# NFCY_BaseBoard.net
KiCad netlist of a schematic drawn in Altium Designer
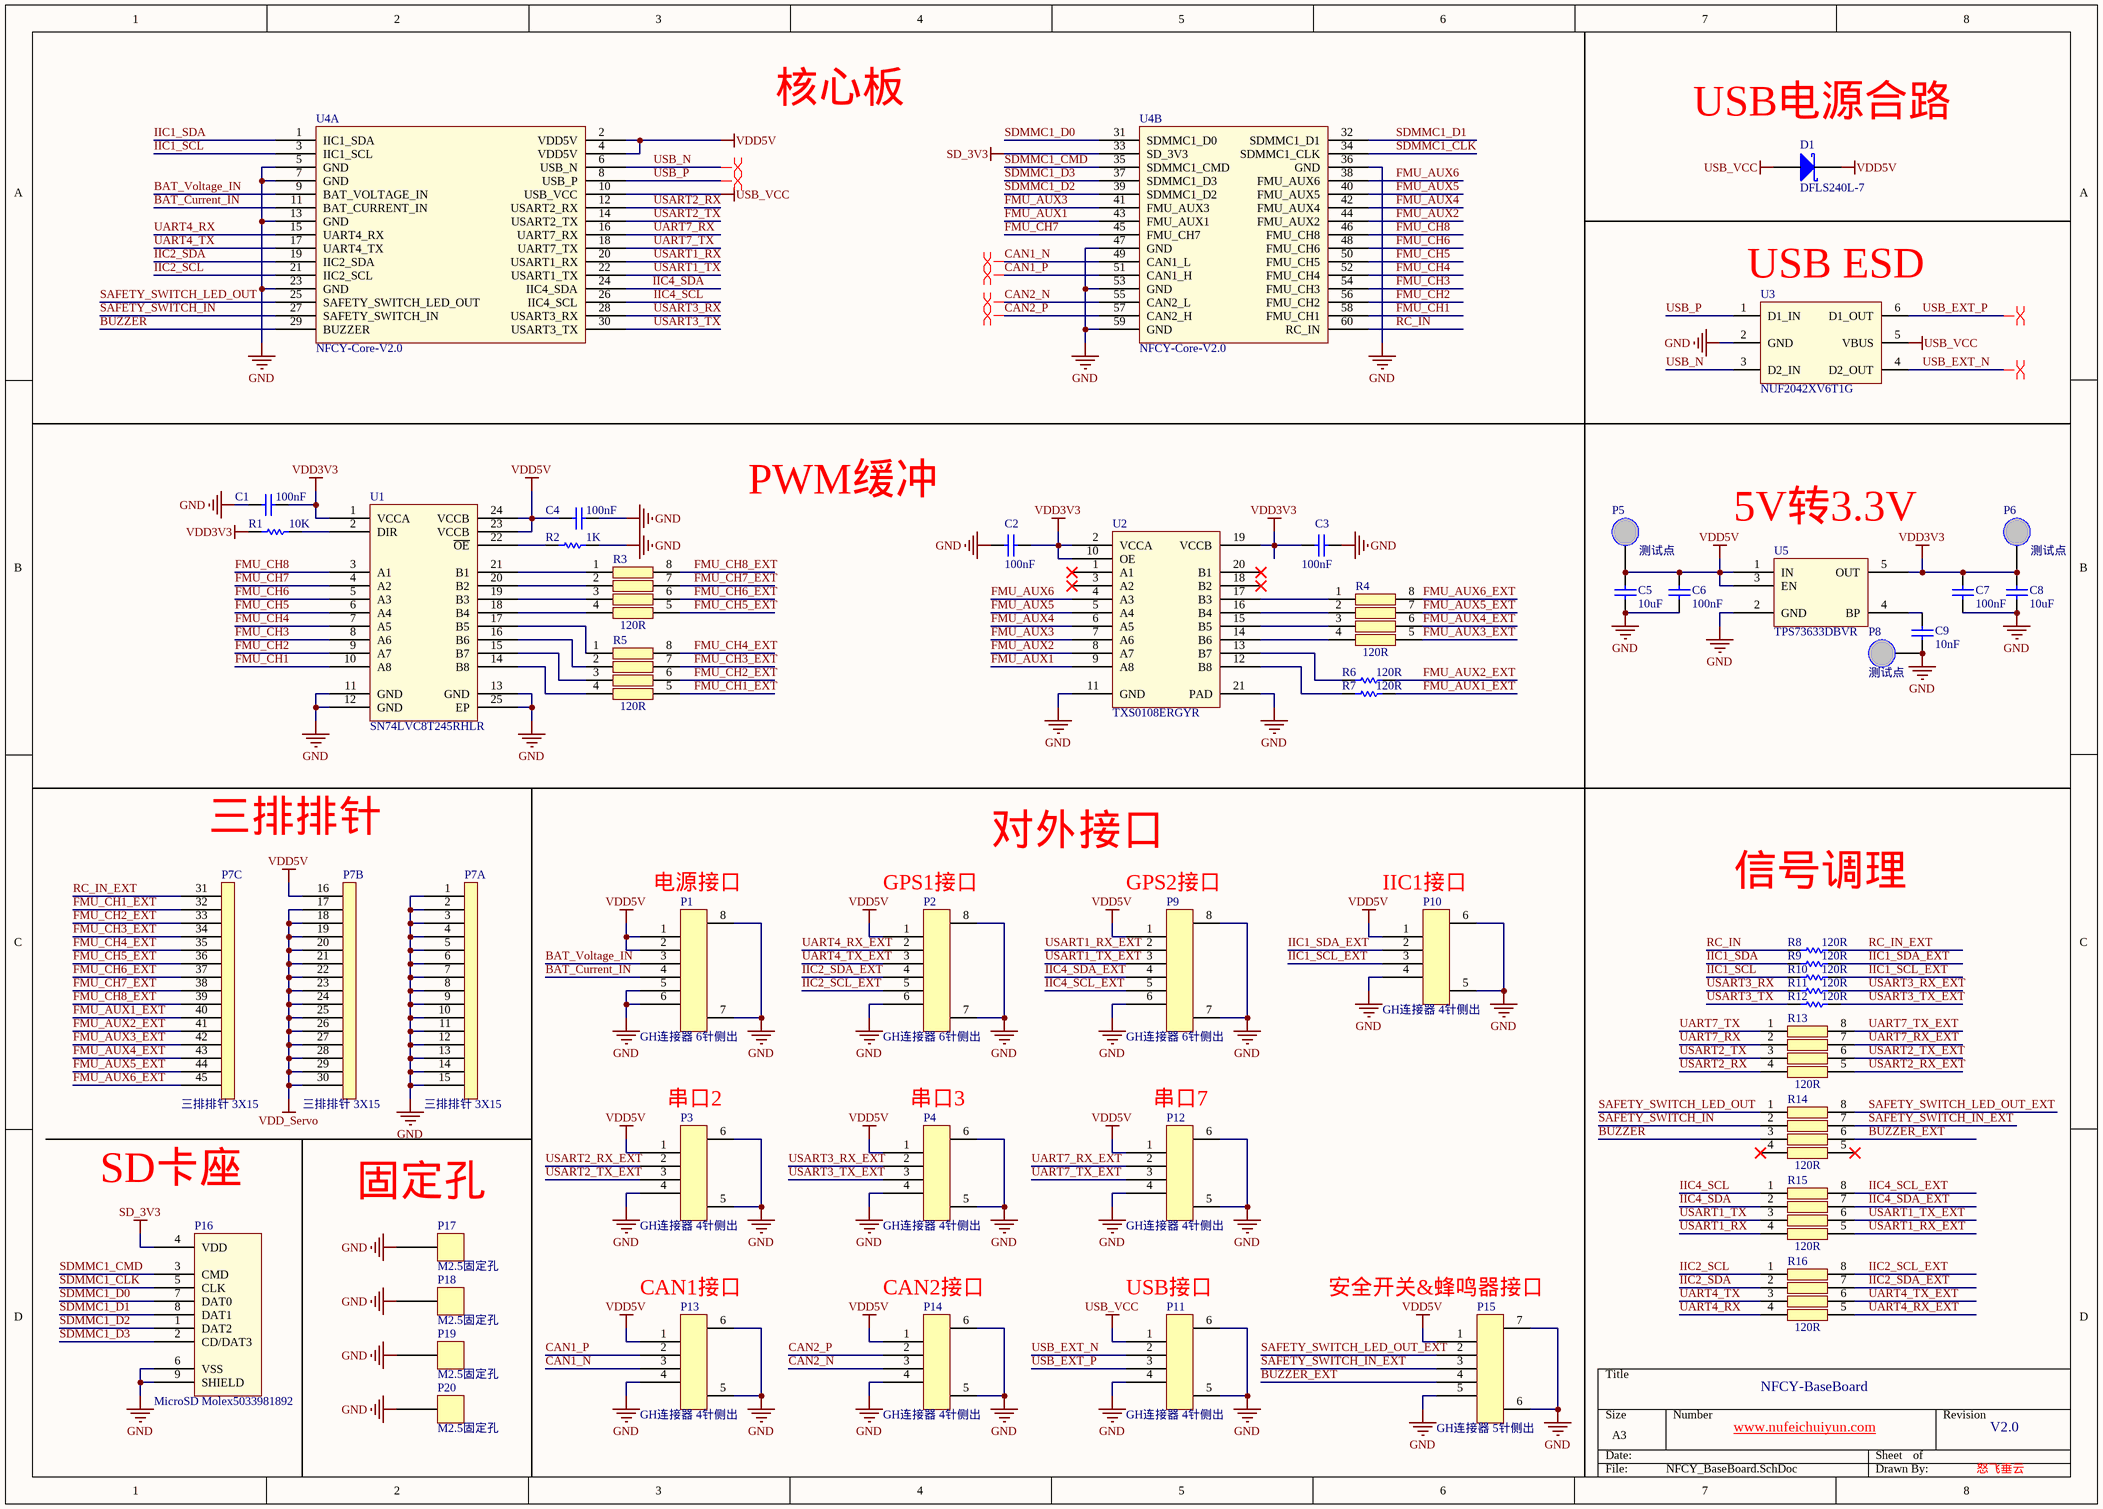
[diagram p0: NFCY_BaseBoard.SchDoc]

(export (version "E")
  (design (tool "Eeschema 10.0.6"))
  (components
    (comp (ref "C1")
      (value "100nF")
      (footprint "CAP0402")
      (description "贴片电容")
      (fields
        (field (name "MANUFACTURER") "SAMSUNG(三星)")
        (field (name "Comment") "CL05B104KO5NNNC")
        (field (name "PUBLISHER") "Altium Limited")
      )
      (libsource (lib "Miscellaneous Devices") (part "Cap"))
    )
    (comp (ref "C2")
      (value "100nF")
      (footprint "CAP0402")
      (description "贴片电容")
      (fields
        (field (name "MANUFACTURER") "SAMSUNG(三星)")
        (field (name "Comment") "CL05B104KO5NNNC")
        (field (name "PUBLISHER") "Altium Limited")
      )
      (libsource (lib "Miscellaneous Devices") (part "Cap"))
    )
    (comp (ref "C3")
      (value "100nF")
      (footprint "CAP0402")
      (description "贴片电容")
      (fields
        (field (name "MANUFACTURER") "SAMSUNG(三星)")
        (field (name "Comment") "CL05B104KO5NNNC")
        (field (name "PUBLISHER") "Altium Limited")
      )
      (libsource (lib "Miscellaneous Devices") (part "Cap"))
    )
    (comp (ref "C4")
      (value "100nF")
      (footprint "CAP0402")
      (description "贴片电容")
      (fields
        (field (name "MANUFACTURER") "SAMSUNG(三星)")
        (field (name "Comment") "CL05B104KO5NNNC")
        (field (name "PUBLISHER") "Altium Limited")
      )
      (libsource (lib "Miscellaneous Devices") (part "Cap"))
    )
    (comp (ref "C5")
      (value "10uF")
      (footprint "CAP0805")
      (description "贴片电容")
      (fields
        (field (name "MANUFACTURER") "SAMSUNG(三星)")
        (field (name "Comment") "CL21A106KAYNNNE")
        (field (name "PUBLISHER") "Altium Limited")
      )
      (libsource (lib "Miscellaneous Devices") (part "Cap"))
    )
    (comp (ref "C6")
      (value "100nF")
      (footprint "CAP0402")
      (description "贴片电容")
      (fields
        (field (name "MANUFACTURER") "SAMSUNG(三星)")
        (field (name "Comment") "CL05B104KO5NNNC")
        (field (name "PUBLISHER") "Altium Limited")
      )
      (libsource (lib "Miscellaneous Devices") (part "Cap"))
    )
    (comp (ref "C7")
      (value "100nF")
      (footprint "CAP0402")
      (description "贴片电容")
      (fields
        (field (name "MANUFACTURER") "SAMSUNG(三星)")
        (field (name "Comment") "CL05B104KO5NNNC")
        (field (name "PUBLISHER") "Altium Limited")
      )
      (libsource (lib "Miscellaneous Devices") (part "Cap"))
    )
    (comp (ref "C8")
      (value "10uF")
      (footprint "CAP0805")
      (description "贴片电容")
      (fields
        (field (name "MANUFACTURER") "SAMSUNG(三星)")
        (field (name "Comment") "CL21A106KAYNNNE")
        (field (name "PUBLISHER") "Altium Limited")
      )
      (libsource (lib "Miscellaneous Devices") (part "Cap"))
    )
    (comp (ref "C9")
      (value "10nF")
      (footprint "CAP0402")
      (description "贴片电容")
      (fields
        (field (name "MANUFACTURER") "YAGEO(国巨)")
        (field (name "Comment") "CC0402KRX7R9BB103")
        (field (name "PUBLISHER") "Altium Limited")
      )
      (libsource (lib "Miscellaneous Devices") (part "Cap"))
    )
    (comp (ref "D1")
      (value "DFLS240L-7")
      (footprint "PwerDI123")
      (description "肖特基二极管")
      (fields (field (name "MANUFACTURER") "DIODES(美台)"))
      (libsource (lib "二极管") (part "DFLS240L-7"))
    )
    (comp (ref "P1")
      (value "GH连接器 6针侧出")
      (footprint "SM06B-GHS-TB")
      (description "连接器")
      (fields (field (name "MANUFACTURER") "JST"))
      (libsource (lib "GH_Connector") (part "GH_6PIN"))
    )
    (comp (ref "P2")
      (value "GH连接器 6针侧出")
      (footprint "SM06B-GHS-TB")
      (description "连接器")
      (fields (field (name "MANUFACTURER") "JST"))
      (libsource (lib "GH_Connector") (part "GH_6PIN"))
    )
    (comp (ref "P3")
      (value "GH连接器 4针侧出")
      (footprint "SM04B-GHS-TB")
      (description "连接器")
      (fields (field (name "MANUFACTURER") "JST"))
      (libsource (lib "GH_Connector") (part "GH_4PIN"))
    )
    (comp (ref "P4")
      (value "GH连接器 4针侧出")
      (footprint "SM04B-GHS-TB")
      (description "连接器")
      (fields (field (name "MANUFACTURER") "JST"))
      (libsource (lib "GH_Connector") (part "GH_4PIN"))
    )
    (comp (ref "P5") (value "测试点") (footprint "PAD0p8MM") (libsource (lib "TestPad") (part "TestPad")))
    (comp (ref "P6") (value "测试点") (footprint "PAD0p8MM") (libsource (lib "TestPad") (part "TestPad")))
    (comp (ref "P7")
      (value "三排排针 3X15")
      (footprint "HDR3X15")
      (description "排针")
      (libsource (lib "排针") (part "三排排针 3X15"))
    )
    (comp (ref "P8") (value "测试点") (footprint "PAD0p8MM") (libsource (lib "TestPad") (part "TestPad")))
    (comp (ref "P9")
      (value "GH连接器 6针侧出")
      (footprint "SM06B-GHS-TB")
      (description "连接器")
      (fields (field (name "MANUFACTURER") "JST"))
      (libsource (lib "GH_Connector") (part "GH_6PIN"))
    )
    (comp (ref "P10")
      (value "GH连接器 4针侧出")
      (footprint "SM04B-GHS-TB")
      (description "连接器")
      (fields (field (name "MANUFACTURER") "JST"))
      (libsource (lib "GH_Connector") (part "GH_4PIN"))
    )
    (comp (ref "P11")
      (value "GH连接器 4针侧出")
      (footprint "SM04B-GHS-TB")
      (description "连接器")
      (fields (field (name "MANUFACTURER") "JST"))
      (libsource (lib "GH_Connector") (part "GH_4PIN"))
    )
    (comp (ref "P12")
      (value "GH连接器 4针侧出")
      (footprint "SM04B-GHS-TB")
      (description "连接器")
      (fields (field (name "MANUFACTURER") "JST"))
      (libsource (lib "GH_Connector") (part "GH_4PIN"))
    )
    (comp (ref "P13")
      (value "GH连接器 4针侧出")
      (footprint "SM04B-GHS-TB")
      (description "连接器")
      (fields (field (name "MANUFACTURER") "JST"))
      (libsource (lib "GH_Connector") (part "GH_4PIN"))
    )
    (comp (ref "P14")
      (value "GH连接器 4针侧出")
      (footprint "SM04B-GHS-TB")
      (description "连接器")
      (fields (field (name "MANUFACTURER") "JST"))
      (libsource (lib "GH_Connector") (part "GH_4PIN"))
    )
    (comp (ref "P15")
      (value "GH连接器 5针侧出")
      (footprint "SM05B-GHS-TB")
      (description "连接器")
      (fields (field (name "MANUFACTURER") "JST"))
      (libsource (lib "GH_Connector") (part "GH_5PIN"))
    )
    (comp (ref "P16")
      (value "MicroSD Molex5033981892")
      (footprint "Molex5033981892")
      (description "MicroSD卡座")
      (fields (field (name "MANUFACTURER") "Molex"))
      (libsource (lib "SD") (part "MicroSD Molex5033981892"))
    )
    (comp (ref "P17") (value "M2.5固定孔") (footprint "M2p5") (libsource (lib "TestPad") (part "Pad")))
    (comp (ref "P18") (value "M2.5固定孔") (footprint "M2p5") (libsource (lib "TestPad") (part "Pad")))
    (comp (ref "P19") (value "M2.5固定孔") (footprint "M2p5") (libsource (lib "TestPad") (part "Pad")))
    (comp (ref "P20") (value "M2.5固定孔") (footprint "M2p5") (libsource (lib "TestPad") (part "Pad")))
    (comp (ref "R1")
      (value "10K")
      (footprint "RES0402")
      (description "贴片电阻")
      (fields
        (field (name "MANUFACTURER") "YAGEO(国巨)")
        (field (name "Comment") "RC0402FR-0710KL")
        (field (name "PUBLISHER") "Altium Limited")
      )
      (libsource (lib "Miscellaneous Devices") (part "Res1"))
    )
    (comp (ref "R2")
      (value "1K")
      (footprint "RES0402")
      (description "贴片电阻")
      (fields
        (field (name "MANUFACTURER") "YAGEO(国巨)")
        (field (name "Comment") "RC0402FR-071KL")
        (field (name "PUBLISHER") "Altium Limited")
      )
      (libsource (lib "Miscellaneous Devices") (part "Res1"))
    )
    (comp (ref "R3")
      (value "120R")
      (footprint "RES0402_x4")
      (description "排阻")
      (fields (field (name "MANUFACTURER") "RALEC(旺诠)") (field (name "Comment") "4D02WGJ0121TCE"))
      (libsource (lib "电阻") (part "排阻_x4"))
    )
    (comp (ref "R4")
      (value "120R")
      (footprint "RES0402_x4")
      (description "排阻")
      (fields (field (name "MANUFACTURER") "RALEC(旺诠)") (field (name "Comment") "4D02WGJ0121TCE"))
      (libsource (lib "电阻") (part "排阻_x4"))
    )
    (comp (ref "R5")
      (value "120R")
      (footprint "RES0402_x4")
      (description "排阻")
      (fields (field (name "MANUFACTURER") "RALEC(旺诠)") (field (name "Comment") "4D02WGJ0121TCE"))
      (libsource (lib "电阻") (part "排阻_x4"))
    )
    (comp (ref "R6")
      (value "120R")
      (footprint "RES0402")
      (description "贴片电阻")
      (fields
        (field (name "MANUFACTURER") "YAGEO(国巨)")
        (field (name "Comment") "RC0402FR-07120RL")
        (field (name "PUBLISHER") "Altium Limited")
      )
      (libsource (lib "Miscellaneous Devices") (part "Res1"))
    )
    (comp (ref "R7")
      (value "120R")
      (footprint "RES0402")
      (description "贴片电阻")
      (fields
        (field (name "MANUFACTURER") "YAGEO(国巨)")
        (field (name "Comment") "RC0402FR-07120RL")
        (field (name "PUBLISHER") "Altium Limited")
      )
      (libsource (lib "Miscellaneous Devices") (part "Res1"))
    )
    (comp (ref "R8")
      (value "120R")
      (footprint "RES0402")
      (description "贴片电阻")
      (fields
        (field (name "MANUFACTURER") "YAGEO(国巨)")
        (field (name "Comment") "RC0402FR-07120RL")
        (field (name "PUBLISHER") "Altium Limited")
      )
      (libsource (lib "Miscellaneous Devices") (part "Res1"))
    )
    (comp (ref "R9")
      (value "120R")
      (footprint "RES0402")
      (description "贴片电阻")
      (fields
        (field (name "MANUFACTURER") "YAGEO(国巨)")
        (field (name "Comment") "RC0402FR-07120RL")
        (field (name "PUBLISHER") "Altium Limited")
      )
      (libsource (lib "Miscellaneous Devices") (part "Res1"))
    )
    (comp (ref "R10")
      (value "120R")
      (footprint "RES0402")
      (description "贴片电阻")
      (fields
        (field (name "MANUFACTURER") "YAGEO(国巨)")
        (field (name "Comment") "RC0402FR-07120RL")
        (field (name "PUBLISHER") "Altium Limited")
      )
      (libsource (lib "Miscellaneous Devices") (part "Res1"))
    )
    (comp (ref "R11")
      (value "120R")
      (footprint "RES0402")
      (description "贴片电阻")
      (fields
        (field (name "MANUFACTURER") "YAGEO(国巨)")
        (field (name "Comment") "RC0402FR-07120RL")
        (field (name "PUBLISHER") "Altium Limited")
      )
      (libsource (lib "Miscellaneous Devices") (part "Res1"))
    )
    (comp (ref "R12")
      (value "120R")
      (footprint "RES0402")
      (description "贴片电阻")
      (fields
        (field (name "MANUFACTURER") "YAGEO(国巨)")
        (field (name "Comment") "RC0402FR-07120RL")
        (field (name "PUBLISHER") "Altium Limited")
      )
      (libsource (lib "Miscellaneous Devices") (part "Res1"))
    )
    (comp (ref "R13")
      (value "120R")
      (footprint "RES0402_x4")
      (description "排阻")
      (fields (field (name "MANUFACTURER") "RALEC(旺诠)") (field (name "Comment") "4D02WGJ0121TCE"))
      (libsource (lib "电阻") (part "排阻_x4"))
    )
    (comp (ref "R14")
      (value "120R")
      (footprint "RES0402_x4")
      (description "排阻")
      (fields (field (name "MANUFACTURER") "RALEC(旺诠)") (field (name "Comment") "4D02WGJ0121TCE"))
      (libsource (lib "电阻") (part "排阻_x4"))
    )
    (comp (ref "R15")
      (value "120R")
      (footprint "RES0402_x4")
      (description "排阻")
      (fields (field (name "MANUFACTURER") "RALEC(旺诠)") (field (name "Comment") "4D02WGJ0121TCE"))
      (libsource (lib "电阻") (part "排阻_x4"))
    )
    (comp (ref "R16")
      (value "120R")
      (footprint "RES0402_x4")
      (description "排阻")
      (fields (field (name "MANUFACTURER") "RALEC(旺诠)") (field (name "Comment") "4D02WGJ0121TCE"))
      (libsource (lib "电阻") (part "排阻_x4"))
    )
    (comp (ref "U1")
      (value "SN74LVC8T245RHLR")
      (footprint "VQFN-24")
      (description "8bit缓冲器芯片")
      (fields (field (name "MANUFACTURER") "TI"))
      (libsource (lib "Chip") (part "SN74LVC8T245RHLR"))
    )
    (comp (ref "U2")
      (value "TXS0108ERGYR")
      (footprint "VQFN-20")
      (description "8位电平转换芯片")
      (fields (field (name "MANUFACTURER") "TI"))
      (libsource (lib "Chip") (part "TXS0108ERGYR"))
    )
    (comp (ref "U3")
      (value "NUF2042XV6T1G")
      (footprint "SOT-563")
      (description "USB ESD保护芯片")
      (fields (field (name "MANUFACTURER") "ON(安森美)"))
      (libsource (lib "Chip") (part "NUF2042XV6T1G"))
    )
    (comp (ref "U4")
      (value "NFCY-Core-V2.0")
      (footprint "NFCY-Core-V2")
      (description "怒飞垂云飞控核心模块")
      (fields (field (name "MANUFACTURER") "怒飞垂云"))
      (libsource (lib "排针") (part "NFCY-Core-V2.0"))
    )
    (comp (ref "U5")
      (value "TPS73633DBVR")
      (footprint "SOT23-5")
      (description "LDO芯片")
      (fields (field (name "MANUFACTURER") "TI"))
      (libsource (lib "Power") (part "TPS73633DBVR"))
    )
  )
  (nets
    (net (code "1") (name "/BAT_Current_IN") (class "Default")
      (node (ref "P1") (pin "4") (pinfunction "4_4") (pintype "passive"))
      (node (ref "U4") (pin "11") (pinfunction "BAT_CURRENT_IN_11") (pintype "passive"))
    )
    (net (code "2") (name "/BAT_Voltage_IN") (class "Default")
      (node (ref "P1") (pin "3") (pinfunction "3_3") (pintype "passive"))
      (node (ref "U4") (pin "9") (pinfunction "BAT_VOLTAGE_IN_9") (pintype "passive"))
    )
    (net (code "3") (name "/BUZZER") (class "Default")
      (node (ref "R14") (pin "3") (pinfunction "3_3") (pintype "passive"))
      (node (ref "U4") (pin "29") (pinfunction "BUZZER_29") (pintype "passive"))
    )
    (net (code "4") (name "/BUZZER_EXT") (class "Default")
      (node (ref "P15") (pin "4") (pinfunction "4_4") (pintype "passive"))
      (node (ref "R14") (pin "6") (pinfunction "6_6") (pintype "passive"))
    )
    (net (code "5") (name "/CAN1_N") (class "Default")
      (node (ref "P13") (pin "3") (pinfunction "3_3") (pintype "passive"))
      (node (ref "U4") (pin "49") (pinfunction "CAN1_L_49") (pintype "passive"))
    )
    (net (code "6") (name "/CAN1_P") (class "Default")
      (node (ref "P13") (pin "2") (pinfunction "2_2") (pintype "passive"))
      (node (ref "U4") (pin "51") (pinfunction "CAN1_H_51") (pintype "passive"))
    )
    (net (code "7") (name "/CAN2_N") (class "Default")
      (node (ref "P14") (pin "3") (pinfunction "3_3") (pintype "passive"))
      (node (ref "U4") (pin "55") (pinfunction "CAN2_L_55") (pintype "passive"))
    )
    (net (code "8") (name "/CAN2_P") (class "Default")
      (node (ref "P14") (pin "2") (pinfunction "2_2") (pintype "passive"))
      (node (ref "U4") (pin "57") (pinfunction "CAN2_H_57") (pintype "passive"))
    )
    (net (code "9") (name "/FMU_AUX1") (class "Default")
      (node (ref "U2") (pin "9") (pinfunction "A8_9") (pintype "passive"))
      (node (ref "U4") (pin "43") (pinfunction "FMU_AUX1_43") (pintype "passive"))
    )
    (net (code "10") (name "/FMU_AUX1_EXT") (class "Default")
      (node (ref "P7") (pin "40") (pinfunction "40_40") (pintype "passive"))
      (node (ref "R7") (pin "1") (pinfunction "1_1") (pintype "passive"))
    )
    (net (code "11") (name "/FMU_AUX2") (class "Default")
      (node (ref "U2") (pin "8") (pinfunction "A7_8") (pintype "passive"))
      (node (ref "U4") (pin "44") (pinfunction "FMU_AUX2_44") (pintype "passive"))
    )
    (net (code "12") (name "/FMU_AUX2_EXT") (class "Default")
      (node (ref "P7") (pin "41") (pinfunction "41_41") (pintype "passive"))
      (node (ref "R6") (pin "1") (pinfunction "1_1") (pintype "passive"))
    )
    (net (code "13") (name "/FMU_AUX3") (class "Default")
      (node (ref "U2") (pin "7") (pinfunction "A6_7") (pintype "passive"))
      (node (ref "U4") (pin "41") (pinfunction "FMU_AUX3_41") (pintype "passive"))
    )
    (net (code "14") (name "/FMU_AUX3_EXT") (class "Default")
      (node (ref "P7") (pin "42") (pinfunction "42_42") (pintype "passive"))
      (node (ref "R4") (pin "5") (pinfunction "5_5") (pintype "passive"))
    )
    (net (code "15") (name "/FMU_AUX4") (class "Default")
      (node (ref "U2") (pin "6") (pinfunction "A5_6") (pintype "passive"))
      (node (ref "U4") (pin "42") (pinfunction "FMU_AUX4_42") (pintype "passive"))
    )
    (net (code "16") (name "/FMU_AUX4_EXT") (class "Default")
      (node (ref "P7") (pin "43") (pinfunction "43_43") (pintype "passive"))
      (node (ref "R4") (pin "6") (pinfunction "6_6") (pintype "passive"))
    )
    (net (code "17") (name "/FMU_AUX5") (class "Default")
      (node (ref "U2") (pin "5") (pinfunction "A4_5") (pintype "passive"))
      (node (ref "U4") (pin "40") (pinfunction "FMU_AUX5_40") (pintype "passive"))
    )
    (net (code "18") (name "/FMU_AUX5_EXT") (class "Default")
      (node (ref "P7") (pin "44") (pinfunction "44_44") (pintype "passive"))
      (node (ref "R4") (pin "7") (pinfunction "7_7") (pintype "passive"))
    )
    (net (code "19") (name "/FMU_AUX6") (class "Default")
      (node (ref "U2") (pin "4") (pinfunction "A3_4") (pintype "passive"))
      (node (ref "U4") (pin "38") (pinfunction "FMU_AUX6_38") (pintype "passive"))
    )
    (net (code "20") (name "/FMU_AUX6_EXT") (class "Default")
      (node (ref "P7") (pin "45") (pinfunction "45_45") (pintype "passive"))
      (node (ref "R4") (pin "8") (pinfunction "8_8") (pintype "passive"))
    )
    (net (code "21") (name "/FMU_CH1") (class "Default")
      (node (ref "U1") (pin "10") (pinfunction "A8_10") (pintype "passive"))
      (node (ref "U4") (pin "58") (pinfunction "FMU_CH1_58") (pintype "passive"))
    )
    (net (code "22") (name "/FMU_CH1_EXT") (class "Default")
      (node (ref "P7") (pin "32") (pinfunction "32_32") (pintype "passive"))
      (node (ref "R5") (pin "5") (pinfunction "5_5") (pintype "passive"))
    )
    (net (code "23") (name "/FMU_CH2") (class "Default")
      (node (ref "U1") (pin "9") (pinfunction "A7_9") (pintype "passive"))
      (node (ref "U4") (pin "56") (pinfunction "FMU_CH2_56") (pintype "passive"))
    )
    (net (code "24") (name "/FMU_CH2_EXT") (class "Default")
      (node (ref "P7") (pin "33") (pinfunction "33_33") (pintype "passive"))
      (node (ref "R5") (pin "6") (pinfunction "6_6") (pintype "passive"))
    )
    (net (code "25") (name "/FMU_CH3") (class "Default")
      (node (ref "U1") (pin "8") (pinfunction "A6_8") (pintype "passive"))
      (node (ref "U4") (pin "54") (pinfunction "FMU_CH3_54") (pintype "passive"))
    )
    (net (code "26") (name "/FMU_CH3_EXT") (class "Default")
      (node (ref "P7") (pin "34") (pinfunction "34_34") (pintype "passive"))
      (node (ref "R5") (pin "7") (pinfunction "7_7") (pintype "passive"))
    )
    (net (code "27") (name "/FMU_CH4") (class "Default")
      (node (ref "U1") (pin "7") (pinfunction "A5_7") (pintype "passive"))
      (node (ref "U4") (pin "52") (pinfunction "FMU_CH4_52") (pintype "passive"))
    )
    (net (code "28") (name "/FMU_CH4_EXT") (class "Default")
      (node (ref "P7") (pin "35") (pinfunction "35_35") (pintype "passive"))
      (node (ref "R5") (pin "8") (pinfunction "8_8") (pintype "passive"))
    )
    (net (code "29") (name "/FMU_CH5") (class "Default")
      (node (ref "U1") (pin "6") (pinfunction "A4_6") (pintype "passive"))
      (node (ref "U4") (pin "50") (pinfunction "FMU_CH5_50") (pintype "passive"))
    )
    (net (code "30") (name "/FMU_CH5_EXT") (class "Default")
      (node (ref "P7") (pin "36") (pinfunction "36_36") (pintype "passive"))
      (node (ref "R3") (pin "5") (pinfunction "5_5") (pintype "passive"))
    )
    (net (code "31") (name "/FMU_CH6") (class "Default")
      (node (ref "U1") (pin "5") (pinfunction "A3_5") (pintype "passive"))
      (node (ref "U4") (pin "48") (pinfunction "FMU_CH6_48") (pintype "passive"))
    )
    (net (code "32") (name "/FMU_CH6_EXT") (class "Default")
      (node (ref "P7") (pin "37") (pinfunction "37_37") (pintype "passive"))
      (node (ref "R3") (pin "6") (pinfunction "6_6") (pintype "passive"))
    )
    (net (code "33") (name "/FMU_CH7") (class "Default")
      (node (ref "U1") (pin "4") (pinfunction "A2_4") (pintype "passive"))
      (node (ref "U4") (pin "45") (pinfunction "FMU_CH7_45") (pintype "passive"))
    )
    (net (code "34") (name "/FMU_CH7_EXT") (class "Default")
      (node (ref "P7") (pin "38") (pinfunction "38_38") (pintype "passive"))
      (node (ref "R3") (pin "7") (pinfunction "7_7") (pintype "passive"))
    )
    (net (code "35") (name "/FMU_CH8") (class "Default")
      (node (ref "U1") (pin "3") (pinfunction "A1_3") (pintype "passive"))
      (node (ref "U4") (pin "46") (pinfunction "FMU_CH8_46") (pintype "passive"))
    )
    (net (code "36") (name "/FMU_CH8_EXT") (class "Default")
      (node (ref "P7") (pin "39") (pinfunction "39_39") (pintype "passive"))
      (node (ref "R3") (pin "8") (pinfunction "8_8") (pintype "passive"))
    )
    (net (code "37") (name "/IIC1_SCL") (class "Default")
      (node (ref "R10") (pin "2") (pinfunction "2_2") (pintype "passive"))
      (node (ref "U4") (pin "3") (pinfunction "IIC1_SCL_3") (pintype "passive"))
    )
    (net (code "38") (name "/IIC1_SCL_EXT") (class "Default")
      (node (ref "P10") (pin "3") (pinfunction "3_3") (pintype "passive"))
      (node (ref "R10") (pin "1") (pinfunction "1_1") (pintype "passive"))
    )
    (net (code "39") (name "/IIC1_SDA") (class "Default")
      (node (ref "R9") (pin "2") (pinfunction "2_2") (pintype "passive"))
      (node (ref "U4") (pin "1") (pinfunction "IIC1_SDA_1") (pintype "passive"))
    )
    (net (code "40") (name "/IIC1_SDA_EXT") (class "Default")
      (node (ref "P10") (pin "2") (pinfunction "2_2") (pintype "passive"))
      (node (ref "R9") (pin "1") (pinfunction "1_1") (pintype "passive"))
    )
    (net (code "41") (name "/IIC2_SCL") (class "Default")
      (node (ref "R16") (pin "1") (pinfunction "1_1") (pintype "passive"))
      (node (ref "U4") (pin "21") (pinfunction "IIC2_SCL_21") (pintype "passive"))
    )
    (net (code "42") (name "/IIC2_SCL_EXT") (class "Default")
      (node (ref "P2") (pin "5") (pinfunction "5_5") (pintype "passive"))
      (node (ref "R16") (pin "8") (pinfunction "8_8") (pintype "passive"))
    )
    (net (code "43") (name "/IIC2_SDA") (class "Default")
      (node (ref "R16") (pin "2") (pinfunction "2_2") (pintype "passive"))
      (node (ref "U4") (pin "19") (pinfunction "IIC2_SDA_19") (pintype "passive"))
    )
    (net (code "44") (name "/IIC2_SDA_EXT") (class "Default")
      (node (ref "P2") (pin "4") (pinfunction "4_4") (pintype "passive"))
      (node (ref "R16") (pin "7") (pinfunction "7_7") (pintype "passive"))
    )
    (net (code "45") (name "/IIC4_SCL") (class "Default")
      (node (ref "R15") (pin "1") (pinfunction "1_1") (pintype "passive"))
      (node (ref "U4") (pin "26") (pinfunction "IIC4_SCL_26") (pintype "passive"))
    )
    (net (code "46") (name "/IIC4_SCL_EXT") (class "Default")
      (node (ref "P9") (pin "5") (pinfunction "5_5") (pintype "passive"))
      (node (ref "R15") (pin "8") (pinfunction "8_8") (pintype "passive"))
    )
    (net (code "47") (name "/IIC4_SDA") (class "Default")
      (node (ref "R15") (pin "2") (pinfunction "2_2") (pintype "passive"))
      (node (ref "U4") (pin "24") (pinfunction "IIC4_SDA_24") (pintype "passive"))
    )
    (net (code "48") (name "/IIC4_SDA_EXT") (class "Default")
      (node (ref "P9") (pin "4") (pinfunction "4_4") (pintype "passive"))
      (node (ref "R15") (pin "7") (pinfunction "7_7") (pintype "passive"))
    )
    (net (code "49") (name "/RC_IN") (class "Default")
      (node (ref "R8") (pin "2") (pinfunction "2_2") (pintype "passive"))
      (node (ref "U4") (pin "60") (pinfunction "RC_IN_60") (pintype "passive"))
    )
    (net (code "50") (name "/RC_IN_EXT") (class "Default")
      (node (ref "P7") (pin "31") (pinfunction "31_31") (pintype "passive"))
      (node (ref "R8") (pin "1") (pinfunction "1_1") (pintype "passive"))
    )
    (net (code "51") (name "/SAFETY_SWITCH_IN") (class "Default")
      (node (ref "R14") (pin "2") (pinfunction "2_2") (pintype "passive"))
      (node (ref "U4") (pin "27") (pinfunction "SAFETY_SWITCH_IN_27") (pintype "passive"))
    )
    (net (code "52") (name "/SAFETY_SWITCH_IN_EXT") (class "Default")
      (node (ref "P15") (pin "3") (pinfunction "3_3") (pintype "passive"))
      (node (ref "R14") (pin "7") (pinfunction "7_7") (pintype "passive"))
    )
    (net (code "53") (name "/SAFETY_SWITCH_LED_OUT") (class "Default")
      (node (ref "R14") (pin "1") (pinfunction "1_1") (pintype "passive"))
      (node (ref "U4") (pin "25") (pinfunction "SAFETY_SWITCH_LED_OUT_25") (pintype "passive"))
    )
    (net (code "54") (name "/SAFETY_SWITCH_LED_OUT_EXT") (class "Default")
      (node (ref "P15") (pin "2") (pinfunction "2_2") (pintype "passive"))
      (node (ref "R14") (pin "8") (pinfunction "8_8") (pintype "passive"))
    )
    (net (code "55") (name "/SDMMC1_CLK") (class "Default")
      (node (ref "P16") (pin "5") (pinfunction "CLK_5") (pintype "passive"))
      (node (ref "U4") (pin "34") (pinfunction "SDMMC1_CLK_34") (pintype "passive"))
    )
    (net (code "56") (name "/SDMMC1_CMD") (class "Default")
      (node (ref "P16") (pin "3") (pinfunction "CMD_3") (pintype "passive"))
      (node (ref "U4") (pin "35") (pinfunction "SDMMC1_CMD_35") (pintype "passive"))
    )
    (net (code "57") (name "/SDMMC1_D0") (class "Default")
      (node (ref "P16") (pin "7") (pinfunction "DAT0_7") (pintype "passive"))
      (node (ref "U4") (pin "31") (pinfunction "SDMMC1_D0_31") (pintype "passive"))
    )
    (net (code "58") (name "/SDMMC1_D1") (class "Default")
      (node (ref "P16") (pin "8") (pinfunction "DAT1_8") (pintype "passive"))
      (node (ref "U4") (pin "32") (pinfunction "SDMMC1_D1_32") (pintype "passive"))
    )
    (net (code "59") (name "/SDMMC1_D2") (class "Default")
      (node (ref "P16") (pin "1") (pinfunction "DAT2_1") (pintype "passive"))
      (node (ref "U4") (pin "39") (pinfunction "SDMMC1_D2_39") (pintype "passive"))
    )
    (net (code "60") (name "/SDMMC1_D3") (class "Default")
      (node (ref "P16") (pin "2") (pinfunction "CD/DAT3_2") (pintype "passive"))
      (node (ref "U4") (pin "37") (pinfunction "SDMMC1_D3_37") (pintype "passive"))
    )
    (net (code "61") (name "/UART4_RX") (class "Default")
      (node (ref "R16") (pin "4") (pinfunction "4_4") (pintype "passive"))
      (node (ref "U4") (pin "15") (pinfunction "UART4_RX_15") (pintype "passive"))
    )
    (net (code "62") (name "/UART4_RX_EXT") (class "Default")
      (node (ref "P2") (pin "2") (pinfunction "2_2") (pintype "passive"))
      (node (ref "R16") (pin "5") (pinfunction "5_5") (pintype "passive"))
    )
    (net (code "63") (name "/UART4_TX") (class "Default")
      (node (ref "R16") (pin "3") (pinfunction "3_3") (pintype "passive"))
      (node (ref "U4") (pin "17") (pinfunction "UART4_TX_17") (pintype "passive"))
    )
    (net (code "64") (name "/UART4_TX_EXT") (class "Default")
      (node (ref "P2") (pin "3") (pinfunction "3_3") (pintype "passive"))
      (node (ref "R16") (pin "6") (pinfunction "6_6") (pintype "passive"))
    )
    (net (code "65") (name "/UART7_RX") (class "Default")
      (node (ref "R13") (pin "2") (pinfunction "2_2") (pintype "passive"))
      (node (ref "U4") (pin "16") (pinfunction "UART7_RX_16") (pintype "passive"))
    )
    (net (code "66") (name "/UART7_RX_EXT") (class "Default")
      (node (ref "P12") (pin "2") (pinfunction "2_2") (pintype "passive"))
      (node (ref "R13") (pin "7") (pinfunction "7_7") (pintype "passive"))
    )
    (net (code "67") (name "/UART7_TX") (class "Default")
      (node (ref "R13") (pin "1") (pinfunction "1_1") (pintype "passive"))
      (node (ref "U4") (pin "18") (pinfunction "UART7_TX_18") (pintype "passive"))
    )
    (net (code "68") (name "/UART7_TX_EXT") (class "Default")
      (node (ref "P12") (pin "3") (pinfunction "3_3") (pintype "passive"))
      (node (ref "R13") (pin "8") (pinfunction "8_8") (pintype "passive"))
    )
    (net (code "69") (name "/USART1_RX") (class "Default")
      (node (ref "R15") (pin "4") (pinfunction "4_4") (pintype "passive"))
      (node (ref "U4") (pin "20") (pinfunction "USART1_RX_20") (pintype "passive"))
    )
    (net (code "70") (name "/USART1_RX_EXT") (class "Default")
      (node (ref "P9") (pin "2") (pinfunction "2_2") (pintype "passive"))
      (node (ref "R15") (pin "5") (pinfunction "5_5") (pintype "passive"))
    )
    (net (code "71") (name "/USART1_TX") (class "Default")
      (node (ref "R15") (pin "3") (pinfunction "3_3") (pintype "passive"))
      (node (ref "U4") (pin "22") (pinfunction "USART1_TX_22") (pintype "passive"))
    )
    (net (code "72") (name "/USART1_TX_EXT") (class "Default")
      (node (ref "P9") (pin "3") (pinfunction "3_3") (pintype "passive"))
      (node (ref "R15") (pin "6") (pinfunction "6_6") (pintype "passive"))
    )
    (net (code "73") (name "/USART2_RX") (class "Default")
      (node (ref "R13") (pin "4") (pinfunction "4_4") (pintype "passive"))
      (node (ref "U4") (pin "12") (pinfunction "USART2_RX_12") (pintype "passive"))
    )
    (net (code "74") (name "/USART2_RX_EXT") (class "Default")
      (node (ref "P3") (pin "2") (pinfunction "2_2") (pintype "passive"))
      (node (ref "R13") (pin "5") (pinfunction "5_5") (pintype "passive"))
    )
    (net (code "75") (name "/USART2_TX") (class "Default")
      (node (ref "R13") (pin "3") (pinfunction "3_3") (pintype "passive"))
      (node (ref "U4") (pin "14") (pinfunction "USART2_TX_14") (pintype "passive"))
    )
    (net (code "76") (name "/USART2_TX_EXT") (class "Default")
      (node (ref "P3") (pin "3") (pinfunction "3_3") (pintype "passive"))
      (node (ref "R13") (pin "6") (pinfunction "6_6") (pintype "passive"))
    )
    (net (code "77") (name "/USART3_RX") (class "Default")
      (node (ref "R11") (pin "2") (pinfunction "2_2") (pintype "passive"))
      (node (ref "U4") (pin "28") (pinfunction "USART3_RX_28") (pintype "passive"))
    )
    (net (code "78") (name "/USART3_RX_EXT") (class "Default")
      (node (ref "P4") (pin "2") (pinfunction "2_2") (pintype "passive"))
      (node (ref "R11") (pin "1") (pinfunction "1_1") (pintype "passive"))
    )
    (net (code "79") (name "/USART3_TX") (class "Default")
      (node (ref "R12") (pin "2") (pinfunction "2_2") (pintype "passive"))
      (node (ref "U4") (pin "30") (pinfunction "USART3_TX_30") (pintype "passive"))
    )
    (net (code "80") (name "/USART3_TX_EXT") (class "Default")
      (node (ref "P4") (pin "3") (pinfunction "3_3") (pintype "passive"))
      (node (ref "R12") (pin "1") (pinfunction "1_1") (pintype "passive"))
    )
    (net (code "81") (name "/USB_EXT_N") (class "Default")
      (node (ref "P11") (pin "2") (pinfunction "2_2") (pintype "passive"))
      (node (ref "U3") (pin "4") (pinfunction "D2_OUT_4") (pintype "passive"))
    )
    (net (code "82") (name "/USB_EXT_P") (class "Default")
      (node (ref "P11") (pin "3") (pinfunction "3_3") (pintype "passive"))
      (node (ref "U3") (pin "6") (pinfunction "D1_OUT_6") (pintype "passive"))
    )
    (net (code "83") (name "/USB_N") (class "Default")
      (node (ref "U3") (pin "3") (pinfunction "D2_IN_3") (pintype "passive"))
      (node (ref "U4") (pin "6") (pinfunction "USB_N_6") (pintype "passive"))
    )
    (net (code "84") (name "/USB_P") (class "Default")
      (node (ref "U3") (pin "1") (pinfunction "D1_IN_1") (pintype "passive"))
      (node (ref "U4") (pin "8") (pinfunction "USB_P_8") (pintype "passive"))
    )
    (net (code "85") (name "GND") (class "Default")
      (node (ref "C1") (pin "1") (pinfunction "1_1") (pintype "passive"))
      (node (ref "C2") (pin "2") (pinfunction "2_2") (pintype "passive"))
      (node (ref "C3") (pin "1") (pinfunction "1_1") (pintype "passive"))
      (node (ref "C4") (pin "1") (pinfunction "1_1") (pintype "passive"))
      (node (ref "C5") (pin "2") (pinfunction "2_2") (pintype "passive"))
      (node (ref "C6") (pin "2") (pinfunction "2_2") (pintype "passive"))
      (node (ref "C7") (pin "2") (pinfunction "2_2") (pintype "passive"))
      (node (ref "C8") (pin "2") (pinfunction "2_2") (pintype "passive"))
      (node (ref "C9") (pin "2") (pinfunction "2_2") (pintype "passive"))
      (node (ref "P1") (pin "5") (pinfunction "5_5") (pintype "passive"))
      (node (ref "P1") (pin "6") (pinfunction "6_6") (pintype "passive"))
      (node (ref "P1") (pin "7") (pinfunction "7_7") (pintype "passive"))
      (node (ref "P1") (pin "8") (pinfunction "8_8") (pintype "passive"))
      (node (ref "P10") (pin "4") (pinfunction "4_4") (pintype "passive"))
      (node (ref "P10") (pin "5") (pinfunction "5_5") (pintype "passive"))
      (node (ref "P10") (pin "6") (pinfunction "6_6") (pintype "passive"))
      (node (ref "P11") (pin "4") (pinfunction "4_4") (pintype "passive"))
      (node (ref "P11") (pin "5") (pinfunction "5_5") (pintype "passive"))
      (node (ref "P11") (pin "6") (pinfunction "6_6") (pintype "passive"))
      (node (ref "P12") (pin "4") (pinfunction "4_4") (pintype "passive"))
      (node (ref "P12") (pin "5") (pinfunction "5_5") (pintype "passive"))
      (node (ref "P12") (pin "6") (pinfunction "6_6") (pintype "passive"))
      (node (ref "P13") (pin "4") (pinfunction "4_4") (pintype "passive"))
      (node (ref "P13") (pin "5") (pinfunction "5_5") (pintype "passive"))
      (node (ref "P13") (pin "6") (pinfunction "6_6") (pintype "passive"))
      (node (ref "P14") (pin "4") (pinfunction "4_4") (pintype "passive"))
      (node (ref "P14") (pin "5") (pinfunction "5_5") (pintype "passive"))
      (node (ref "P14") (pin "6") (pinfunction "6_6") (pintype "passive"))
      (node (ref "P15") (pin "5") (pinfunction "5_5") (pintype "passive"))
      (node (ref "P15") (pin "6") (pinfunction "6_6") (pintype "passive"))
      (node (ref "P15") (pin "7") (pinfunction "7_7") (pintype "passive"))
      (node (ref "P16") (pin "6") (pinfunction "VSS_6") (pintype "passive"))
      (node (ref "P16") (pin "9") (pinfunction "SHIELD_9") (pintype "passive"))
      (node (ref "P17") (pin "1") (pinfunction "1_1") (pintype "passive"))
      (node (ref "P18") (pin "1") (pinfunction "1_1") (pintype "passive"))
      (node (ref "P19") (pin "1") (pinfunction "1_1") (pintype "passive"))
      (node (ref "P2") (pin "6") (pinfunction "6_6") (pintype "passive"))
      (node (ref "P2") (pin "7") (pinfunction "7_7") (pintype "passive"))
      (node (ref "P2") (pin "8") (pinfunction "8_8") (pintype "passive"))
      (node (ref "P20") (pin "1") (pinfunction "1_1") (pintype "passive"))
      (node (ref "P3") (pin "4") (pinfunction "4_4") (pintype "passive"))
      (node (ref "P3") (pin "5") (pinfunction "5_5") (pintype "passive"))
      (node (ref "P3") (pin "6") (pinfunction "6_6") (pintype "passive"))
      (node (ref "P4") (pin "4") (pinfunction "4_4") (pintype "passive"))
      (node (ref "P4") (pin "5") (pinfunction "5_5") (pintype "passive"))
      (node (ref "P4") (pin "6") (pinfunction "6_6") (pintype "passive"))
      (node (ref "P7") (pin "1") (pintype "passive"))
      (node (ref "P7") (pin "10") (pintype "passive"))
      (node (ref "P7") (pin "11") (pintype "passive"))
      (node (ref "P7") (pin "12") (pintype "passive"))
      (node (ref "P7") (pin "13") (pinfunction "13_13") (pintype "passive"))
      (node (ref "P7") (pin "14") (pinfunction "14_14") (pintype "passive"))
      (node (ref "P7") (pin "15") (pinfunction "15_15") (pintype "passive"))
      (node (ref "P7") (pin "2") (pintype "passive"))
      (node (ref "P7") (pin "3") (pintype "passive"))
      (node (ref "P7") (pin "4") (pintype "passive"))
      (node (ref "P7") (pin "5") (pintype "passive"))
      (node (ref "P7") (pin "6") (pintype "passive"))
      (node (ref "P7") (pin "7") (pintype "passive"))
      (node (ref "P7") (pin "8") (pintype "passive"))
      (node (ref "P7") (pin "9") (pintype "passive"))
      (node (ref "P8") (pin "1") (pinfunction "1_1") (pintype "passive"))
      (node (ref "P9") (pin "6") (pinfunction "6_6") (pintype "passive"))
      (node (ref "P9") (pin "7") (pinfunction "7_7") (pintype "passive"))
      (node (ref "P9") (pin "8") (pinfunction "8_8") (pintype "passive"))
      (node (ref "R2") (pin "2") (pinfunction "2_2") (pintype "passive"))
      (node (ref "U1") (pin "11") (pinfunction "GND_11") (pintype "passive"))
      (node (ref "U1") (pin "12") (pinfunction "GND_12") (pintype "passive"))
      (node (ref "U1") (pin "13") (pinfunction "GND_13") (pintype "passive"))
      (node (ref "U1") (pin "25") (pinfunction "EP_25") (pintype "passive"))
      (node (ref "U2") (pin "11") (pinfunction "GND_11") (pintype "passive"))
      (node (ref "U2") (pin "21") (pinfunction "PAD_21") (pintype "passive"))
      (node (ref "U3") (pin "2") (pinfunction "GND_2") (pintype "passive"))
      (node (ref "U4") (pin "13") (pinfunction "GND_13") (pintype "passive"))
      (node (ref "U4") (pin "23") (pinfunction "GND_23") (pintype "passive"))
      (node (ref "U4") (pin "36") (pinfunction "GND_36") (pintype "passive"))
      (node (ref "U4") (pin "47") (pinfunction "GND_47") (pintype "passive"))
      (node (ref "U4") (pin "5") (pinfunction "GND_5") (pintype "passive"))
      (node (ref "U4") (pin "53") (pinfunction "GND_53") (pintype "passive"))
      (node (ref "U4") (pin "59") (pinfunction "GND_59") (pintype "passive"))
      (node (ref "U4") (pin "7") (pinfunction "GND_7") (pintype "passive"))
      (node (ref "U5") (pin "2") (pinfunction "GND_2") (pintype "passive"))
    )
    (net (code "86") (name "Net-(U1-B1)") (class "Default")
      (node (ref "R3") (pin "1") (pinfunction "1_1") (pintype "passive"))
      (node (ref "U1") (pin "21") (pinfunction "B1_21") (pintype "passive"))
    )
    (net (code "87") (name "Net-(U1-B2)") (class "Default")
      (node (ref "R3") (pin "2") (pinfunction "2_2") (pintype "passive"))
      (node (ref "U1") (pin "20") (pinfunction "B2_20") (pintype "passive"))
    )
    (net (code "88") (name "Net-(U1-B3)") (class "Default")
      (node (ref "R3") (pin "3") (pinfunction "3_3") (pintype "passive"))
      (node (ref "U1") (pin "19") (pinfunction "B3_19") (pintype "passive"))
    )
    (net (code "89") (name "Net-(U1-B4)") (class "Default")
      (node (ref "R3") (pin "4") (pinfunction "4_4") (pintype "passive"))
      (node (ref "U1") (pin "18") (pinfunction "B4_18") (pintype "passive"))
    )
    (net (code "90") (name "Net-(U1-B5)") (class "Default")
      (node (ref "R5") (pin "1") (pinfunction "1_1") (pintype "passive"))
      (node (ref "U1") (pin "17") (pinfunction "B5_17") (pintype "passive"))
    )
    (net (code "91") (name "Net-(U1-B6)") (class "Default")
      (node (ref "R5") (pin "2") (pinfunction "2_2") (pintype "passive"))
      (node (ref "U1") (pin "16") (pinfunction "B6_16") (pintype "passive"))
    )
    (net (code "92") (name "Net-(U1-B7)") (class "Default")
      (node (ref "R5") (pin "3") (pinfunction "3_3") (pintype "passive"))
      (node (ref "U1") (pin "15") (pinfunction "B7_15") (pintype "passive"))
    )
    (net (code "93") (name "Net-(U1-B8)") (class "Default")
      (node (ref "R5") (pin "4") (pinfunction "4_4") (pintype "passive"))
      (node (ref "U1") (pin "14") (pinfunction "B8_14") (pintype "passive"))
    )
    (net (code "94") (name "Net-(U1-DIR)") (class "Default")
      (node (ref "R1") (pin "1") (pinfunction "1_1") (pintype "passive"))
      (node (ref "U1") (pin "2") (pinfunction "DIR_2") (pintype "passive"))
    )
    (net (code "95") (name "Net-(U1-~{OE})") (class "Default")
      (node (ref "R2") (pin "1") (pinfunction "1_1") (pintype "passive"))
      (node (ref "U1") (pin "22") (pinfunction "~{OE}_22") (pintype "passive"))
    )
    (net (code "96") (name "Net-(U2-B3)") (class "Default")
      (node (ref "R4") (pin "1") (pinfunction "1_1") (pintype "passive"))
      (node (ref "U2") (pin "17") (pinfunction "B3_17") (pintype "passive"))
    )
    (net (code "97") (name "Net-(U2-B4)") (class "Default")
      (node (ref "R4") (pin "2") (pinfunction "2_2") (pintype "passive"))
      (node (ref "U2") (pin "16") (pinfunction "B4_16") (pintype "passive"))
    )
    (net (code "98") (name "Net-(U2-B5)") (class "Default")
      (node (ref "R4") (pin "3") (pinfunction "3_3") (pintype "passive"))
      (node (ref "U2") (pin "15") (pinfunction "B5_15") (pintype "passive"))
    )
    (net (code "99") (name "Net-(U2-B6)") (class "Default")
      (node (ref "R4") (pin "4") (pinfunction "4_4") (pintype "passive"))
      (node (ref "U2") (pin "14") (pinfunction "B6_14") (pintype "passive"))
    )
    (net (code "100") (name "Net-(U2-B7)") (class "Default")
      (node (ref "R6") (pin "2") (pinfunction "2_2") (pintype "passive"))
      (node (ref "U2") (pin "13") (pinfunction "B7_13") (pintype "passive"))
    )
    (net (code "101") (name "Net-(U2-B8)") (class "Default")
      (node (ref "R7") (pin "2") (pinfunction "2_2") (pintype "passive"))
      (node (ref "U2") (pin "12") (pinfunction "B8_12") (pintype "passive"))
    )
    (net (code "102") (name "Net-(U5-BP)") (class "Default")
      (node (ref "C9") (pin "1") (pinfunction "1_1") (pintype "passive"))
      (node (ref "U5") (pin "4") (pinfunction "BP_4") (pintype "passive"))
    )
    (net (code "103") (name "SD_3V3") (class "Default")
      (node (ref "P16") (pin "4") (pinfunction "VDD_4") (pintype "passive"))
      (node (ref "U4") (pin "33") (pinfunction "SD_3V3_33") (pintype "passive"))
    )
    (net (code "104") (name "USB_VCC") (class "Default")
      (node (ref "D1") (pin "2") (pinfunction "2_2") (pintype "passive"))
      (node (ref "P11") (pin "1") (pinfunction "1_1") (pintype "passive"))
      (node (ref "U3") (pin "5") (pinfunction "VBUS_5") (pintype "passive"))
      (node (ref "U4") (pin "10") (pinfunction "USB_VCC_10") (pintype "passive"))
    )
    (net (code "105") (name "VDD3V3") (class "Default")
      (node (ref "C1") (pin "2") (pinfunction "2_2") (pintype "passive"))
      (node (ref "C2") (pin "1") (pinfunction "1_1") (pintype "passive"))
      (node (ref "C3") (pin "2") (pinfunction "2_2") (pintype "passive"))
      (node (ref "C7") (pin "1") (pinfunction "1_1") (pintype "passive"))
      (node (ref "C8") (pin "1") (pinfunction "1_1") (pintype "passive"))
      (node (ref "P6") (pin "1") (pinfunction "1_1") (pintype "passive"))
      (node (ref "R1") (pin "2") (pinfunction "2_2") (pintype "passive"))
      (node (ref "U1") (pin "1") (pinfunction "VCCA_1") (pintype "passive"))
      (node (ref "U2") (pin "10") (pinfunction "OE_10") (pintype "passive"))
      (node (ref "U2") (pin "19") (pinfunction "VCCB_19") (pintype "passive"))
      (node (ref "U2") (pin "2") (pinfunction "VCCA_2") (pintype "passive"))
      (node (ref "U5") (pin "5") (pinfunction "OUT_5") (pintype "passive"))
    )
    (net (code "106") (name "VDD5V") (class "Default")
      (node (ref "C4") (pin "2") (pinfunction "2_2") (pintype "passive"))
      (node (ref "C5") (pin "1") (pinfunction "1_1") (pintype "passive"))
      (node (ref "C6") (pin "1") (pinfunction "1_1") (pintype "passive"))
      (node (ref "D1") (pin "1") (pinfunction "1_1") (pintype "passive"))
      (node (ref "P1") (pin "1") (pinfunction "1_1") (pintype "passive"))
      (node (ref "P1") (pin "2") (pinfunction "2_2") (pintype "passive"))
      (node (ref "P10") (pin "1") (pinfunction "1_1") (pintype "passive"))
      (node (ref "P12") (pin "1") (pinfunction "1_1") (pintype "passive"))
      (node (ref "P13") (pin "1") (pinfunction "1_1") (pintype "passive"))
      (node (ref "P14") (pin "1") (pinfunction "1_1") (pintype "passive"))
      (node (ref "P15") (pin "1") (pinfunction "1_1") (pintype "passive"))
      (node (ref "P2") (pin "1") (pinfunction "1_1") (pintype "passive"))
      (node (ref "P3") (pin "1") (pinfunction "1_1") (pintype "passive"))
      (node (ref "P4") (pin "1") (pinfunction "1_1") (pintype "passive"))
      (node (ref "P5") (pin "1") (pinfunction "1_1") (pintype "passive"))
      (node (ref "P7") (pin "16") (pinfunction "16_16") (pintype "passive"))
      (node (ref "P9") (pin "1") (pinfunction "1_1") (pintype "passive"))
      (node (ref "U1") (pin "23") (pinfunction "VCCB_23") (pintype "passive"))
      (node (ref "U1") (pin "24") (pinfunction "VCCB_24") (pintype "passive"))
      (node (ref "U4") (pin "2") (pinfunction "VDD5V_2") (pintype "passive"))
      (node (ref "U4") (pin "4") (pinfunction "VDD5V_4") (pintype "passive"))
      (node (ref "U5") (pin "1") (pinfunction "IN_1") (pintype "passive"))
      (node (ref "U5") (pin "3") (pinfunction "EN_3") (pintype "passive"))
    )
    (net (code "107") (name "VDD_Servo") (class "Default")
      (node (ref "P7") (pin "17") (pinfunction "17_17") (pintype "passive"))
      (node (ref "P7") (pin "18") (pinfunction "18_18") (pintype "passive"))
      (node (ref "P7") (pin "19") (pinfunction "19_19") (pintype "passive"))
      (node (ref "P7") (pin "20") (pinfunction "20_20") (pintype "passive"))
      (node (ref "P7") (pin "21") (pinfunction "21_21") (pintype "passive"))
      (node (ref "P7") (pin "22") (pinfunction "22_22") (pintype "passive"))
      (node (ref "P7") (pin "23") (pinfunction "23_23") (pintype "passive"))
      (node (ref "P7") (pin "24") (pinfunction "24_24") (pintype "passive"))
      (node (ref "P7") (pin "25") (pinfunction "25_25") (pintype "passive"))
      (node (ref "P7") (pin "26") (pinfunction "26_26") (pintype "passive"))
      (node (ref "P7") (pin "27") (pinfunction "27_27") (pintype "passive"))
      (node (ref "P7") (pin "28") (pinfunction "28_28") (pintype "passive"))
      (node (ref "P7") (pin "29") (pinfunction "29_29") (pintype "passive"))
      (node (ref "P7") (pin "30") (pinfunction "30_30") (pintype "passive"))
    )
    (net (code "108") (name "unconnected-(R14-Pad4)") (class "Default")
      (node (ref "R14") (pin "4") (pinfunction "4_4") (pintype "passive+no_connect"))
    )
    (net (code "109") (name "unconnected-(R14-Pad5)") (class "Default")
      (node (ref "R14") (pin "5") (pinfunction "5_5") (pintype "passive+no_connect"))
    )
    (net (code "110") (name "unconnected-(U2-A1-Pad1)") (class "Default")
      (node (ref "U2") (pin "1") (pinfunction "A1_1") (pintype "passive+no_connect"))
    )
    (net (code "111") (name "unconnected-(U2-A2-Pad3)") (class "Default")
      (node (ref "U2") (pin "3") (pinfunction "A2_3") (pintype "passive+no_connect"))
    )
    (net (code "112") (name "unconnected-(U2-B1-Pad20)") (class "Default")
      (node (ref "U2") (pin "20") (pinfunction "B1_20") (pintype "passive+no_connect"))
    )
    (net (code "113") (name "unconnected-(U2-B2-Pad18)") (class "Default")
      (node (ref "U2") (pin "18") (pinfunction "B2_18") (pintype "passive+no_connect"))
    )
  )
)
